# RS485_FD.net
KiCad netlist of a schematic drawn in Altium Designer
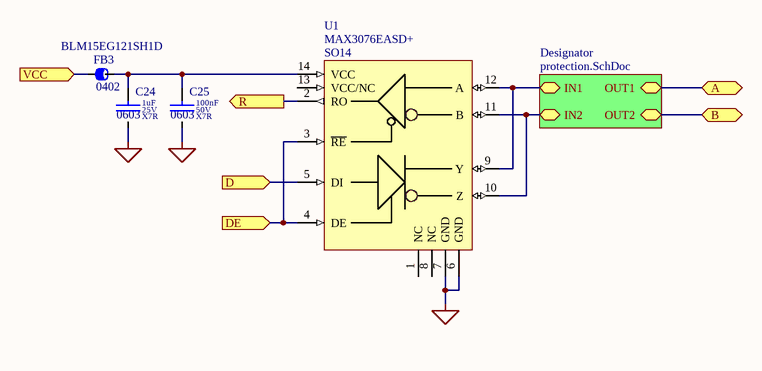
[diagram p0: RS485_FD.SchDoc]

(export (version "E")
  (design (tool "Eeschema 10.0.6"))
  (components
    (comp (ref "C24")
      (value "1uF")
      (footprint "C_0603_1608")
      (description "Capacitor")
      (fields
        (field (name "DIELECTRIC") "X7R")
        (field (name "VOLTAGE") "25V")
        (field (name "SCH_FOOTPRINT") "0603")
        (field (name "PART NUMBER") "C_1uF_25V_X7R_0603_10")
        (field (name "MANUFACTURER") "Samsung")
      )
      (libsource (lib "Library") (part "C"))
    )
    (comp (ref "C25")
      (value "100nF")
      (footprint "C_0603_1608")
      (description "Capacitor")
      (fields
        (field (name "DIELECTRIC") "X7R")
        (field (name "VOLTAGE") "50V")
        (field (name "SCH_FOOTPRINT") "0603")
        (field (name "PART NUMBER") "C_100nF_50V_X7R_0603_5")
        (field (name "MANUFACTURER") "Samsung")
      )
      (libsource (lib "Library") (part "C"))
    )
    (comp (ref "FB3")
      (value "Ferrite bead")
      (footprint "FB_0402_1005")
      (description "Ferrite Bead")
      (fields
        (field (name "PART NUMBER") "FB_BLM15EG121SH1D")
        (field (name "SCH_FOOTPRINT") "0402")
        (field (name "MANUFACTURER") "Murata")
        (field (name "MANUFACTURER PART NUMBER") "BLM15EG121SH1D")
      )
      (libsource (lib "Library") (part "FB"))
    )
    (comp (ref "U1")
      (value "MAX3076EASD+")
      (footprint "SOP14_SO14_SOIC14_4X9X18")
      (fields
        (field (name "SCH_FOOTPRINT") "SO14")
        (field (name "PART NUMBER") "U_MAX3076EASD+")
        (field (name "MANUFACTURER") "Maxim Integrated")
        (field (name "Comment") "MAX3076 Series 16 Mbps 6 V Full Duplex SMT RS 485 Transceiver - SOIC-14")
      )
      (libsource (lib "Library") (part "U_RS485_FD_GENERIC"))
    )
  )
  (nets
    (net (code "3") (name "/D") (class "Default")
      (node (ref "U1") (pin "5") (pinfunction "DI_5") (pintype "input"))
    )
    (net (code "4") (name "/DE") (class "Default")
      (node (ref "U1") (pin "3") (pinfunction "~{RE}_3") (pintype "input"))
      (node (ref "U1") (pin "4") (pinfunction "DE_4") (pintype "input"))
    )
    (net (code "5") (name "/IN1") (class "Default")
      (node (ref "U1") (pin "12") (pinfunction "A_12") (pintype "bidirectional"))
      (node (ref "U1") (pin "9") (pinfunction "Y_9") (pintype "bidirectional"))
    )
    (net (code "6") (name "/IN2") (class "Default")
      (node (ref "U1") (pin "10") (pinfunction "Z_10") (pintype "bidirectional"))
      (node (ref "U1") (pin "11") (pinfunction "B_11") (pintype "bidirectional"))
    )
    (net (code "7") (name "/R") (class "Default")
      (node (ref "U1") (pin "2") (pinfunction "RO_2") (pintype "output"))
    )
    (net (code "8") (name "/VCC") (class "Default") (node (ref "FB3") (pin "1") (pintype "input")))
    (net (code "9") (name "GND") (class "Default")
      (node (ref "C24") (pin "2") (pinfunction "2_2") (pintype "passive"))
      (node (ref "C25") (pin "2") (pinfunction "2_2") (pintype "passive"))
      (node (ref "U1") (pin "6") (pinfunction "GND_6") (pintype "power_in"))
      (node (ref "U1") (pin "7") (pinfunction "GND_7") (pintype "power_in"))
    )
    (net (code "10") (name "Net-(U1-VCC)") (class "Default")
      (node (ref "C24") (pin "1") (pinfunction "1_1") (pintype "passive"))
      (node (ref "C25") (pin "1") (pinfunction "1_1") (pintype "passive"))
      (node (ref "FB3") (pin "2") (pintype "output"))
      (node (ref "U1") (pin "14") (pinfunction "VCC_14") (pintype "input"))
    )
    (net (code "11") (name "unconnected-(U1-NC-Pad1)") (class "Default")
      (node (ref "U1") (pin "1") (pinfunction "NC_1") (pintype "passive"))
    )
    (net (code "12") (name "unconnected-(U1-NC-Pad8)") (class "Default")
      (node (ref "U1") (pin "8") (pinfunction "NC_8") (pintype "passive"))
    )
    (net (code "13") (name "unconnected-(U1-VCC{slash}NC-Pad13)") (class "Default")
      (node (ref "U1") (pin "13") (pinfunction "VCC/NC_13") (pintype "input"))
    )
  )
)
